# Sheet1.net
KiCad netlist of a schematic drawn in Altium Designer
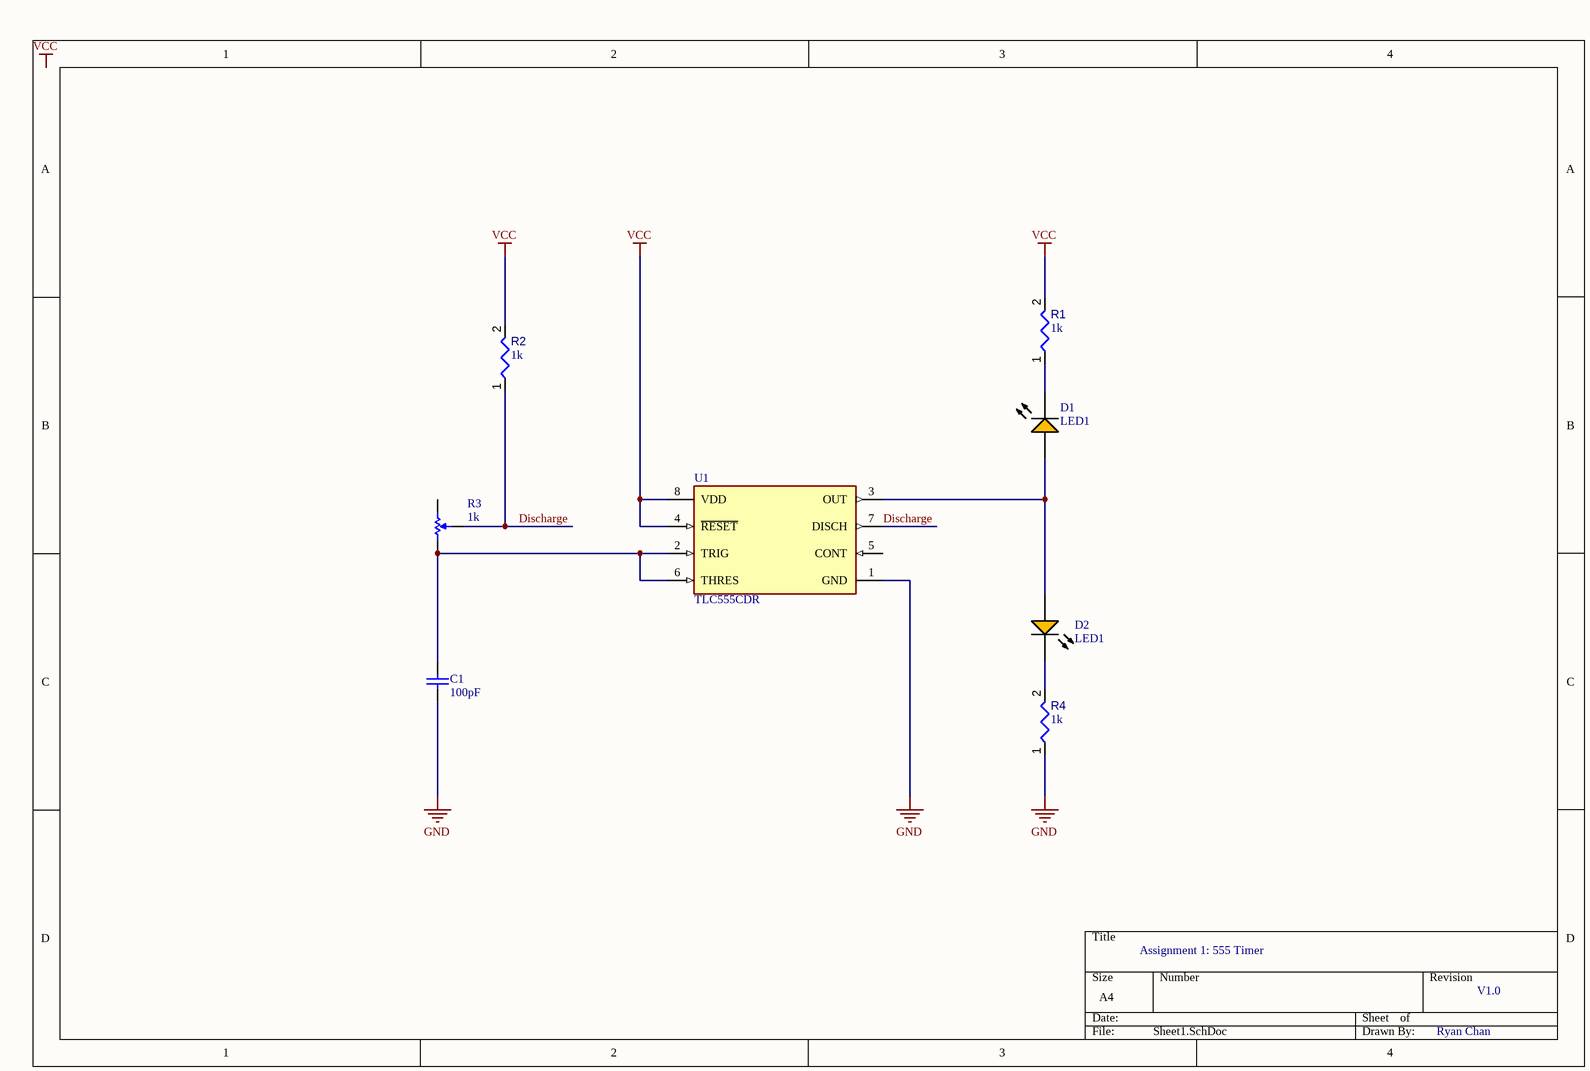
[diagram p0: Sheet1.SchDoc]

(export (version "E")
  (design (tool "Eeschema 10.0.6"))
  (components
    (comp (ref "C1")
      (value "100pF")
      (footprint "CAPC1608X90X35NL10T15")
      (fields (field (name "PART NUMBER") "GRM1885C1H101JA01D") (field (name "MANUFACTURER") "Murata"))
      (libsource (lib "Altium Content Vault") (part "CAP"))
    )
    (comp (ref "D1")
      (value "LED1")
      (footprint "AVAG-HSMX-C190_V")
      (description "LED Uni-Color Amber, 60 mW, 20 mA, -40 to 85 degC, 2-Pin SMD, RoHS, Tape and Reel")
      (fields (field (name "MANUFACTURER") "Avago") (field (name "POWER") "60mW"))
      (libsource (lib "University of California, Davis") (part "LED-AMBER-AK-2"))
    )
    (comp (ref "D2")
      (value "LED1")
      (footprint "AVAG-HSMX-C190_V")
      (description "LED Uni-Color Amber, 60 mW, 20 mA, -40 to 85 degC, 2-Pin SMD, RoHS, Tape and Reel")
      (fields (field (name "MANUFACTURER") "Avago") (field (name "POWER") "60mW"))
      (libsource (lib "University of California, Davis") (part "LED-AMBER-AK-2"))
    )
    (comp (ref "R1")
      (value "Resistor 1K +/-5 % 0402 63 mW")
      (footprint "RESC0402(1005)_L")
      (description "Chip Resistor, 1 kOhms, +/-5 %, 63 mW, -55 to 155 degC, 0402")
      (fields (field (name "POWER") "63mW") (field (name "TOLERANCE") "5%") (field (name "R4") "1k"))
      (libsource (lib "University of California, Davis") (part "RES-2"))
    )
    (comp (ref "R2")
      (value "Resistor 1K +/-5 % 0402 63 mW")
      (footprint "RESC0402(1005)_L")
      (description "Chip Resistor, 1 kOhms, +/-5 %, 63 mW, -55 to 155 degC, 0402")
      (fields (field (name "POWER") "63mW") (field (name "TOLERANCE") "5%") (field (name "R4") "1k"))
      (libsource (lib "University of California, Davis") (part "RES-2"))
    )
    (comp (ref "R3")
      (value "1k")
      (footprint "BOUR-3296W-1-3")
      (description "Square Trimpot(R) Trimming Potentiometer, 1000 Ohm, -55 to 125 degC, 3-Pin THD, RoHS, Tube")
      (fields (field (name "TOLERANCE") "1%"))
      (libsource (lib "Altium Content Vault") (part "RES-ADJ-3"))
    )
    (comp (ref "R4")
      (value "Resistor 1K +/-5 % 0402 63 mW")
      (footprint "RESC0402(1005)_L")
      (description "Chip Resistor, 1 kOhms, +/-5 %, 63 mW, -55 to 155 degC, 0402")
      (fields (field (name "POWER") "63mW") (field (name "TOLERANCE") "5%") (field (name "R4") "1k"))
      (libsource (lib "University of California, Davis") (part "RES-2"))
    )
    (comp (ref "U1")
      (value "TLC555CDR")
      (footprint "FP-D0008A-IPC_B")
      (description "IC OSC SGL TIMER 2.1MHZ 8-SOIC")
      (libsource (lib "Altium Content Vault") (part "fd1638d23bf5e420a54176ee4f8e783"))
    )
  )
  (nets
    (net (code "1") (name "/Discharge") (class "Default")
      (node (ref "R2") (pin "1") (pinfunction "1_1") (pintype "passive"))
      (node (ref "R3") (pin "3") (pinfunction "TAP_3") (pintype "passive"))
      (node (ref "U1") (pin "7") (pinfunction "DISCH_7") (pintype "output"))
    )
    (net (code "2") (name "GND") (class "Default")
      (node (ref "C1") (pin "1") (pinfunction "1_1") (pintype "passive"))
      (node (ref "R4") (pin "1") (pinfunction "1_1") (pintype "passive"))
      (node (ref "U1") (pin "1") (pinfunction "GND_1") (pintype "power_in"))
    )
    (net (code "3") (name "Net-(D1-A)") (class "Default")
      (node (ref "D1") (pin "1") (pinfunction "A_1") (pintype "passive"))
      (node (ref "D2") (pin "1") (pinfunction "A_1") (pintype "passive"))
      (node (ref "U1") (pin "3") (pinfunction "OUT_3") (pintype "output"))
    )
    (net (code "4") (name "Net-(D1-K)") (class "Default")
      (node (ref "D1") (pin "2") (pinfunction "K_2") (pintype "passive"))
      (node (ref "R1") (pin "1") (pinfunction "1_1") (pintype "passive"))
    )
    (net (code "5") (name "Net-(D2-K)") (class "Default")
      (node (ref "D2") (pin "2") (pinfunction "K_2") (pintype "passive"))
      (node (ref "R4") (pin "2") (pinfunction "2_2") (pintype "passive"))
    )
    (net (code "6") (name "Net-(R3-A)") (class "Default")
      (node (ref "C1") (pin "2") (pinfunction "2_2") (pintype "passive"))
      (node (ref "R3") (pin "1") (pinfunction "A_1") (pintype "passive"))
      (node (ref "U1") (pin "2") (pinfunction "TRIG_2") (pintype "input"))
      (node (ref "U1") (pin "6") (pinfunction "THRES_6") (pintype "input"))
    )
    (net (code "7") (name "VCC") (class "Default")
      (node (ref "R1") (pin "2") (pinfunction "2_2") (pintype "passive"))
      (node (ref "R2") (pin "2") (pinfunction "2_2") (pintype "passive"))
      (node (ref "U1") (pin "4") (pinfunction "~{RESET}_4") (pintype "input"))
      (node (ref "U1") (pin "8") (pinfunction "VDD_8") (pintype "power_in"))
    )
    (net (code "8") (name "unconnected-(R3-B-Pad2)") (class "Default")
      (node (ref "R3") (pin "2") (pinfunction "B_2") (pintype "passive"))
    )
    (net (code "9") (name "unconnected-(U1-CONT-Pad5)") (class "Default")
      (node (ref "U1") (pin "5") (pinfunction "CONT_5") (pintype "input"))
    )
  )
)
